# ESP32.net
KiCad netlist of a schematic drawn in Altium Designer
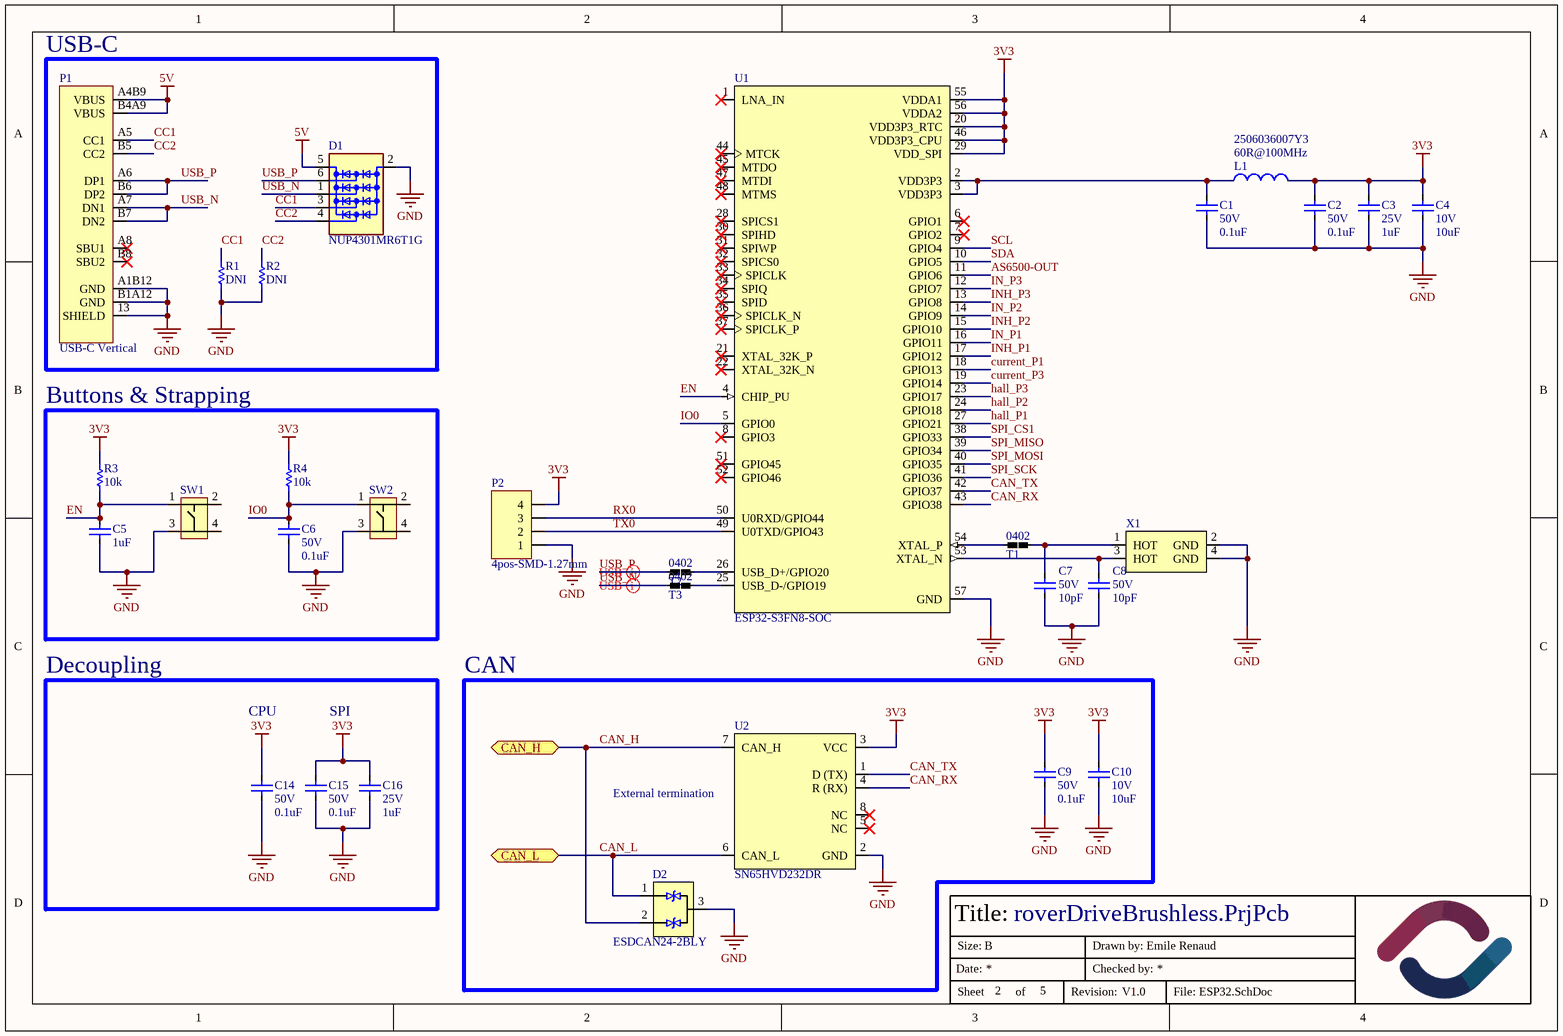
[diagram p0: ESP32.SchDoc]

(export (version "E")
  (design (tool "Eeschema 10.0.6"))
  (components
    (comp (ref "C1")
      (value "0.1uF")
      (footprint "CAPACITOR-0603")
      (description "Capacitor-0603-0.1uF-50V-X7R")
      (fields (field (name "VOLT") "50V"))
      (libsource (lib "Capacitors") (part "Capacitor-0603-0.1uF-50V-X7R"))
    )
    (comp (ref "C2")
      (value "0.1uF")
      (footprint "CAPACITOR-0603")
      (description "Capacitor-0603-0.1uF-50V-X7R")
      (fields (field (name "VOLT") "50V"))
      (libsource (lib "Capacitors") (part "Capacitor-0603-0.1uF-50V-X7R"))
    )
    (comp (ref "C3")
      (value "1uF")
      (footprint "CAPACITOR-0603")
      (description "Capacitor-0603-1uF-25V-X5R")
      (fields (field (name "VOLT") "25V"))
      (libsource (lib "Capacitors") (part "Capacitor-0603-1uF-25V-X5R"))
    )
    (comp (ref "C4")
      (value "10uF")
      (footprint "CAPACITOR-0603")
      (description "10 µF ±20% 10V Ceramic Capacitor X5R 0603 (1608 Metric)")
      (fields (field (name "VOLT") "10V") (field (name "Comment") "Capacitor-0603-10uF-10V-X5R"))
      (libsource (lib "Capacitors") (part "Capacitor-0603-10uF-10V-X5R"))
    )
    (comp (ref "C5")
      (value "1uF")
      (footprint "CAPACITOR-0603")
      (description "Capacitor-0603-1uF-25V-X5R")
      (libsource (lib "Capacitors") (part "Capacitor-0603-1uF-25V-X5R"))
    )
    (comp (ref "C6")
      (value "0.1uF")
      (footprint "CAPACITOR-0603")
      (description "Capacitor-0603-0.1uF-50V-X7R")
      (fields (field (name "VOLT") "50V"))
      (libsource (lib "Capacitors") (part "Capacitor-0603-0.1uF-50V-X7R"))
    )
    (comp (ref "C7")
      (value "10pF")
      (footprint "CAPACITOR-0402")
      (description "Capacitor-0402-10pF-50V-C0G")
      (fields (field (name "VOLT") "50V"))
      (libsource (lib "Capacitors") (part "Capacitor-0402-10pF-50V-C0G"))
    )
    (comp (ref "C8")
      (value "10pF")
      (footprint "CAPACITOR-0402")
      (description "Capacitor-0402-10pF-50V-C0G")
      (fields (field (name "VOLT") "50V"))
      (libsource (lib "Capacitors") (part "Capacitor-0402-10pF-50V-C0G"))
    )
    (comp (ref "C9")
      (value "0.1uF")
      (footprint "CAPACITOR-0603")
      (description "Capacitor-0603-0.1uF-50V-X7R")
      (fields (field (name "VOLT") "50V"))
      (libsource (lib "Capacitors") (part "Capacitor-0603-0.1uF-50V-X7R"))
    )
    (comp (ref "C10")
      (value "10uF")
      (footprint "CAPACITOR-0603")
      (description "10 µF ±20% 10V Ceramic Capacitor X5R 0603 (1608 Metric)")
      (fields (field (name "VOLT") "10V") (field (name "Comment") "Capacitor-0603-10uF-10V-X5R"))
      (libsource (lib "Capacitors") (part "Capacitor-0603-10uF-10V-X5R"))
    )
    (comp (ref "C14")
      (value "0.1uF")
      (footprint "CAPACITOR-0603")
      (description "Capacitor-0603-0.1uF-50V-X7R")
      (fields (field (name "VOLT") "50V"))
      (libsource (lib "Capacitors") (part "Capacitor-0603-0.1uF-50V-X7R"))
    )
    (comp (ref "C15")
      (value "0.1uF")
      (footprint "CAPACITOR-0603")
      (description "Capacitor-0603-0.1uF-50V-X7R")
      (fields (field (name "VOLT") "50V"))
      (libsource (lib "Capacitors") (part "Capacitor-0603-0.1uF-50V-X7R"))
    )
    (comp (ref "C16")
      (value "1uF")
      (footprint "CAPACITOR-0603")
      (description "Capacitor-0603-1uF-25V-X5R")
      (fields (field (name "VOLT") "25V"))
      (libsource (lib "Capacitors") (part "Capacitor-0603-1uF-25V-X5R"))
    )
    (comp (ref "D1")
      (value "NUP4301MR6T1G")
      (footprint "SOT-23-6")
      (description "4CH Clamp Ipp Tvs Diode Surface Mount SOT23-6 (SC74)")
      (libsource (lib "diodes") (part "NUP4301MR6T1G"))
    )
    (comp (ref "D2")
      (value "ESDCAN24-2BLY")
      (footprint "SOT-23-3")
      (description "55V Clamp 6A (8/20µs) Ipp Tvs Diode Surface Mount SOT-23")
      (libsource (lib "diodes-tvs") (part "ESDCAN24-2BLY"))
    )
    (comp (ref "L1")
      (value "2506036007Y3")
      (footprint "CAPACITOR-0603")
      (description "60 Ohms @ 100 MHz 1 Signal Line Ferrite Bead 0603 (1608 Metric) 3A 40mOhm")
      (fields (field (name "ALTIUM_VALUE") "60R@100MHz"))
      (libsource (lib "Inductors") (part "2506036007Y3"))
    )
    (comp (ref "P1")
      (value "USB-C Vertical")
      (footprint "GCT_USB4145-03-0230-C_REVA2")
      (description "USB4145-03-0230-C\r\n5A USB USB 2.0 Receptacle")
      (libsource (lib "PC-connector") (part "USB-C Vertical"))
    )
    (comp (ref "P2")
      (value "4pos-SMD-1.27mm")
      (footprint "HDR1X4-SMD-50mils")
      (description "4pos SMD 1.27mm")
      (libsource (lib "Header") (part "4pos-SMD-1.27mm"))
    )
    (comp (ref "R1")
      (value "DNI")
      (footprint "RESISTOR-0603")
      (description "0603 footprint DO NOT INSTALL")
      (fields (field (name "Comment") "Resistor-0603-5.1k"))
      (libsource (lib "Resistors") (part "Resistor-0603-DNI"))
    )
    (comp (ref "R2")
      (value "DNI")
      (footprint "RESISTOR-0603")
      (description "0603 footprint DO NOT INSTALL")
      (fields (field (name "Comment") "Resistor-0603-5.1k"))
      (libsource (lib "Resistors") (part "Resistor-0603-DNI"))
    )
    (comp (ref "R3")
      (value "10k")
      (footprint "Resistor-0603")
      (description "Resistor0603-10k")
      (fields (field (name "Comment") "SMT resistor"))
      (libsource (lib "Resistors") (part "Resistor0603-10k"))
    )
    (comp (ref "R4")
      (value "10k")
      (footprint "Resistor-0603")
      (description "Resistor0603-10k")
      (fields (field (name "Comment") "SMT resistor"))
      (libsource (lib "Resistors") (part "Resistor0603-10k"))
    )
    (comp (ref "SW1")
      (value "PTS815 SJM 250 SMTR LFS")
      (footprint "SW4_PTS815 SJM 250 SMTR LFS_CNK")
      (description "TACT 4.2 X 3.2, 2.5 MM H, 180GF,")
      (libsource (lib "THTPushButtonSwitches") (part "PTS815 SJM 250 SMTR LFS"))
    )
    (comp (ref "SW2")
      (value "PTS815 SJM 250 SMTR LFS")
      (footprint "SW4_PTS815 SJM 250 SMTR LFS_CNK")
      (description "TACT 4.2 X 3.2, 2.5 MM H, 180GF,")
      (libsource (lib "THTPushButtonSwitches") (part "PTS815 SJM 250 SMTR LFS"))
    )
    (comp (ref "T1")
      (value "NetTie_0402")
      (footprint "NetTie-0402")
      (libsource (lib "JumpersAndHoles") (part "NetTie_0402"))
    )
    (comp (ref "T2")
      (value "NetTie_0402")
      (footprint "NetTie-0402")
      (libsource (lib "JumpersAndHoles") (part "NetTie_0402"))
    )
    (comp (ref "T3")
      (value "NetTie_0402")
      (footprint "NetTie-0402")
      (libsource (lib "JumpersAndHoles") (part "NetTie_0402"))
    )
    (comp (ref "U1")
      (value "ESP32-S3FN8-SOC")
      (footprint "VFQFN-56 Exposed Pad")
      (fields (field (name "MF") "Espressif Systems") (field (name "MP") "ESP32-S3FN8"))
      (libsource (lib "Microcontrollers") (part "ESP32-S3FN8-SOC"))
    )
    (comp (ref "U2")
      (value "SN65HVD232DR")
      (footprint "SOIC-8")
      (description "1/1 Transceiver Half CANbus 8-SOIC")
      (libsource (lib "Transceiver") (part "SN65HVD232DR"))
    )
    (comp (ref "X1")
      (value "CX2016DB40000D0FLJCC")
      (footprint "4-SMD")
      (description "40 MHz ±10ppm Crystal 8pF 50 Ohms 4-SMD, No Lead")
      (libsource (lib "Crystals") (part "CX2016DB40000D0FLJCC"))
    )
  )
  (nets
    (net (code "1") (name "/AS6500-OUT") (class "Default")
      (node (ref "U1") (pin "11") (pinfunction "GPIO6_11") (pintype "bidirectional"))
    )
    (net (code "2") (name "/CAN_H") (class "Default")
      (node (ref "D2") (pin "2") (pinfunction "GND_2") (pintype "passive"))
      (node (ref "U2") (pin "7") (pinfunction "CAN_H_7") (pintype "passive"))
    )
    (net (code "3") (name "/CAN_L") (class "Default")
      (node (ref "D2") (pin "1") (pinfunction "L2_1") (pintype "passive"))
      (node (ref "U2") (pin "6") (pinfunction "CAN_L_6") (pintype "passive"))
    )
    (net (code "4") (name "/CAN_RX") (class "Default")
      (node (ref "U1") (pin "43") (pinfunction "GPIO38_43") (pintype "bidirectional"))
      (node (ref "U2") (pin "4") (pinfunction "R_(RX)_4") (pintype "passive"))
    )
    (net (code "5") (name "/CAN_TX") (class "Default")
      (node (ref "U1") (pin "42") (pinfunction "GPIO37_42") (pintype "bidirectional"))
      (node (ref "U2") (pin "1") (pinfunction "D_(TX)_1") (pintype "passive"))
    )
    (net (code "6") (name "/CC1") (class "Default")
      (node (ref "D1") (pin "3") (pinfunction "L3_3") (pintype "passive"))
      (node (ref "P1") (pin "A5") (pinfunction "CC1_A5") (pintype "passive"))
      (node (ref "R1") (pin "2") (pinfunction "2_2") (pintype "passive"))
    )
    (net (code "7") (name "/CC2") (class "Default")
      (node (ref "D1") (pin "4") (pinfunction "L4_4") (pintype "passive"))
      (node (ref "P1") (pin "B5") (pinfunction "CC2_B5") (pintype "passive"))
      (node (ref "R2") (pin "2") (pinfunction "2_2") (pintype "passive"))
    )
    (net (code "8") (name "/EN") (class "Default")
      (node (ref "C5") (pin "2") (pinfunction "2_2") (pintype "passive"))
      (node (ref "R3") (pin "1") (pinfunction "1_1") (pintype "passive"))
      (node (ref "SW1") (pin "1") (pinfunction "1_1") (pintype "passive"))
      (node (ref "U1") (pin "4") (pinfunction "CHIP_PU_4") (pintype "input"))
    )
    (net (code "9") (name "/INH_P1") (class "Default")
      (node (ref "U1") (pin "17") (pinfunction "GPIO12_17") (pintype "bidirectional"))
    )
    (net (code "10") (name "/INH_P2") (class "Default")
      (node (ref "U1") (pin "15") (pinfunction "GPIO10_15") (pintype "bidirectional"))
    )
    (net (code "11") (name "/INH_P3") (class "Default")
      (node (ref "U1") (pin "13") (pinfunction "GPIO8_13") (pintype "bidirectional"))
    )
    (net (code "12") (name "/IN_P1") (class "Default")
      (node (ref "U1") (pin "16") (pinfunction "GPIO11_16") (pintype "bidirectional"))
    )
    (net (code "13") (name "/IN_P2") (class "Default")
      (node (ref "U1") (pin "14") (pinfunction "GPIO9_14") (pintype "bidirectional"))
    )
    (net (code "14") (name "/IN_P3") (class "Default")
      (node (ref "U1") (pin "12") (pinfunction "GPIO7_12") (pintype "bidirectional"))
    )
    (net (code "15") (name "/IO0") (class "Default")
      (node (ref "C6") (pin "2") (pinfunction "2_2") (pintype "passive"))
      (node (ref "R4") (pin "1") (pinfunction "1_1") (pintype "passive"))
      (node (ref "SW2") (pin "1") (pinfunction "1_1") (pintype "passive"))
      (node (ref "U1") (pin "5") (pinfunction "GPIO0_5") (pintype "bidirectional"))
    )
    (net (code "16") (name "/RX0") (class "Default")
      (node (ref "P2") (pin "3") (pinfunction "3_3") (pintype "passive"))
      (node (ref "U1") (pin "50") (pinfunction "U0RXD/GPIO44_50") (pintype "bidirectional"))
    )
    (net (code "17") (name "/SCL") (class "Default")
      (node (ref "U1") (pin "9") (pinfunction "GPIO4_9") (pintype "bidirectional"))
    )
    (net (code "18") (name "/SDA") (class "Default")
      (node (ref "U1") (pin "10") (pinfunction "GPIO5_10") (pintype "bidirectional"))
    )
    (net (code "19") (name "/SPI_CS1") (class "Default")
      (node (ref "U1") (pin "38") (pinfunction "GPIO33_38") (pintype "bidirectional"))
    )
    (net (code "20") (name "/SPI_MISO") (class "Default")
      (node (ref "U1") (pin "39") (pinfunction "GPIO34_39") (pintype "bidirectional"))
    )
    (net (code "21") (name "/SPI_MOSI") (class "Default")
      (node (ref "U1") (pin "40") (pinfunction "GPIO35_40") (pintype "bidirectional"))
    )
    (net (code "22") (name "/SPI_SCK") (class "Default")
      (node (ref "U1") (pin "41") (pinfunction "GPIO36_41") (pintype "bidirectional"))
    )
    (net (code "23") (name "/TX0") (class "Default")
      (node (ref "P2") (pin "2") (pinfunction "2_2") (pintype "passive"))
      (node (ref "U1") (pin "49") (pinfunction "U0TXD/GPIO43_49") (pintype "bidirectional"))
    )
    (net (code "24") (name "/USB_N") (class "Default")
      (node (ref "D1") (pin "1") (pinfunction "L2_1") (pintype "passive"))
      (node (ref "P1") (pin "A7") (pinfunction "DN1_A7") (pintype "passive"))
      (node (ref "P1") (pin "B7") (pinfunction "DN2_B7") (pintype "passive"))
      (node (ref "T3") (pin "2") (pinfunction "2_2") (pintype "passive"))
    )
    (net (code "25") (name "/USB_P") (class "Default")
      (node (ref "D1") (pin "6") (pinfunction "L1_6") (pintype "passive"))
      (node (ref "P1") (pin "A6") (pinfunction "DP1_A6") (pintype "passive"))
      (node (ref "P1") (pin "B6") (pinfunction "DP2_B6") (pintype "passive"))
      (node (ref "T2") (pin "2") (pinfunction "2_2") (pintype "passive"))
    )
    (net (code "26") (name "/current_P1") (class "Default")
      (node (ref "U1") (pin "18") (pinfunction "GPIO13_18") (pintype "bidirectional"))
    )
    (net (code "27") (name "/current_P3") (class "Default")
      (node (ref "U1") (pin "19") (pinfunction "GPIO14_19") (pintype "bidirectional"))
    )
    (net (code "28") (name "/hall_P1") (class "Default")
      (node (ref "U1") (pin "27") (pinfunction "GPIO21_27") (pintype "bidirectional"))
    )
    (net (code "29") (name "/hall_P2") (class "Default")
      (node (ref "U1") (pin "24") (pinfunction "GPIO18_24") (pintype "bidirectional"))
    )
    (net (code "30") (name "/hall_P3") (class "Default")
      (node (ref "U1") (pin "23") (pinfunction "GPIO17_23") (pintype "bidirectional"))
    )
    (net (code "31") (name "3V3") (class "Default")
      (node (ref "C10") (pin "2") (pinfunction "2_2") (pintype "passive"))
      (node (ref "C14") (pin "2") (pinfunction "2_2") (pintype "passive"))
      (node (ref "C15") (pin "2") (pinfunction "2_2") (pintype "passive"))
      (node (ref "C16") (pin "2") (pinfunction "2_2") (pintype "passive"))
      (node (ref "C2") (pin "2") (pinfunction "2_2") (pintype "passive"))
      (node (ref "C3") (pin "2") (pinfunction "2_2") (pintype "passive"))
      (node (ref "C4") (pin "2") (pinfunction "2_2") (pintype "passive"))
      (node (ref "C9") (pin "2") (pinfunction "2_2") (pintype "passive"))
      (node (ref "L1") (pin "2") (pinfunction "2_2") (pintype "passive"))
      (node (ref "P2") (pin "4") (pinfunction "4_4") (pintype "passive"))
      (node (ref "R3") (pin "2") (pinfunction "2_2") (pintype "passive"))
      (node (ref "R4") (pin "2") (pinfunction "2_2") (pintype "passive"))
      (node (ref "U1") (pin "20") (pinfunction "VDD3P3_RTC_20") (pintype "power_in"))
      (node (ref "U1") (pin "29") (pinfunction "VDD_SPI_29") (pintype "power_in"))
      (node (ref "U1") (pin "46") (pinfunction "VDD3P3_CPU_46") (pintype "power_in"))
      (node (ref "U1") (pin "55") (pinfunction "VDDA1_55") (pintype "power_in"))
      (node (ref "U1") (pin "56") (pinfunction "VDDA2_56") (pintype "power_in"))
      (node (ref "U2") (pin "3") (pinfunction "VCC_3") (pintype "passive"))
    )
    (net (code "32") (name "5V") (class "Default")
      (node (ref "D1") (pin "5") (pinfunction "VDD_5") (pintype "passive"))
      (node (ref "P1") (pin "A4B9") (pinfunction "VBUS_A4B9") (pintype "passive"))
      (node (ref "P1") (pin "B4A9") (pinfunction "VBUS_B4A9") (pintype "passive"))
    )
    (net (code "33") (name "GND") (class "Default")
      (node (ref "C1") (pin "1") (pinfunction "1_1") (pintype "passive"))
      (node (ref "C10") (pin "1") (pinfunction "1_1") (pintype "passive"))
      (node (ref "C14") (pin "1") (pinfunction "1_1") (pintype "passive"))
      (node (ref "C15") (pin "1") (pinfunction "1_1") (pintype "passive"))
      (node (ref "C16") (pin "1") (pinfunction "1_1") (pintype "passive"))
      (node (ref "C2") (pin "1") (pinfunction "1_1") (pintype "passive"))
      (node (ref "C3") (pin "1") (pinfunction "1_1") (pintype "passive"))
      (node (ref "C4") (pin "1") (pinfunction "1_1") (pintype "passive"))
      (node (ref "C5") (pin "1") (pinfunction "1_1") (pintype "passive"))
      (node (ref "C6") (pin "1") (pinfunction "1_1") (pintype "passive"))
      (node (ref "C7") (pin "1") (pinfunction "1_1") (pintype "passive"))
      (node (ref "C8") (pin "1") (pinfunction "1_1") (pintype "passive"))
      (node (ref "C9") (pin "1") (pinfunction "1_1") (pintype "passive"))
      (node (ref "D1") (pin "2") (pinfunction "GND_2") (pintype "passive"))
      (node (ref "D2") (pin "3") (pinfunction "L3_3") (pintype "passive"))
      (node (ref "P1") (pin "13") (pinfunction "SHIELD_13") (pintype "passive"))
      (node (ref "P1") (pin "A1B12") (pinfunction "GND_A1B12") (pintype "passive"))
      (node (ref "P1") (pin "B1A12") (pinfunction "GND_B1A12") (pintype "passive"))
      (node (ref "P2") (pin "1") (pinfunction "1_1") (pintype "passive"))
      (node (ref "R1") (pin "1") (pinfunction "1_1") (pintype "passive"))
      (node (ref "R2") (pin "1") (pinfunction "1_1") (pintype "passive"))
      (node (ref "SW1") (pin "3") (pinfunction "3_3") (pintype "passive"))
      (node (ref "SW2") (pin "3") (pinfunction "3_3") (pintype "passive"))
      (node (ref "U1") (pin "57") (pinfunction "GND_57") (pintype "power_in"))
      (node (ref "U2") (pin "2") (pinfunction "GND_2") (pintype "passive"))
      (node (ref "X1") (pin "2") (pinfunction "GND_2") (pintype "passive"))
      (node (ref "X1") (pin "4") (pinfunction "GND_4") (pintype "passive"))
    )
    (net (code "34") (name "Net-(C1-Pad2)") (class "Default")
      (node (ref "C1") (pin "2") (pinfunction "2_2") (pintype "passive"))
      (node (ref "L1") (pin "1") (pinfunction "1_1") (pintype "passive"))
      (node (ref "U1") (pin "2") (pinfunction "VDD3P3_2") (pintype "power_in"))
      (node (ref "U1") (pin "3") (pinfunction "VDD3P3_3") (pintype "power_in"))
    )
    (net (code "35") (name "Net-(C7-Pad2)") (class "Default")
      (node (ref "C7") (pin "2") (pinfunction "2_2") (pintype "passive"))
      (node (ref "T1") (pin "1") (pinfunction "1_1") (pintype "passive"))
      (node (ref "X1") (pin "1") (pinfunction "HOT_1") (pintype "passive"))
    )
    (net (code "36") (name "Net-(U1-USB_D+{slash}GPIO20)") (class "Default")
      (node (ref "T2") (pin "1") (pinfunction "1_1") (pintype "passive"))
      (node (ref "U1") (pin "26") (pinfunction "USB_D+/GPIO20_26") (pintype "bidirectional"))
    )
    (net (code "37") (name "Net-(U1-USB_D-{slash}GPIO19)") (class "Default")
      (node (ref "T3") (pin "1") (pinfunction "1_1") (pintype "passive"))
      (node (ref "U1") (pin "25") (pinfunction "USB_D-/GPIO19_25") (pintype "bidirectional"))
    )
    (net (code "38") (name "Net-(U1-XTAL_N)") (class "Default")
      (node (ref "C8") (pin "2") (pinfunction "2_2") (pintype "passive"))
      (node (ref "U1") (pin "53") (pinfunction "XTAL_N_53") (pintype "output"))
      (node (ref "X1") (pin "3") (pinfunction "HOT_3") (pintype "passive"))
    )
    (net (code "39") (name "Net-(U1-XTAL_P)") (class "Default")
      (node (ref "T1") (pin "2") (pinfunction "2_2") (pintype "passive"))
      (node (ref "U1") (pin "54") (pinfunction "XTAL_P_54") (pintype "input"))
    )
    (net (code "40") (name "unconnected-(P1-SBU1-PadA8)") (class "Default")
      (node (ref "P1") (pin "A8") (pinfunction "SBU1_A8") (pintype "passive+no_connect"))
    )
    (net (code "41") (name "unconnected-(P1-SBU2-PadB8)") (class "Default")
      (node (ref "P1") (pin "B8") (pinfunction "SBU2_B8") (pintype "passive+no_connect"))
    )
    (net (code "42") (name "unconnected-(SW1-Pad2)") (class "Default")
      (node (ref "SW1") (pin "2") (pinfunction "2_2") (pintype "passive"))
    )
    (net (code "43") (name "unconnected-(SW1-Pad4)") (class "Default")
      (node (ref "SW1") (pin "4") (pinfunction "4_4") (pintype "passive"))
    )
    (net (code "44") (name "unconnected-(SW2-Pad2)") (class "Default")
      (node (ref "SW2") (pin "2") (pinfunction "2_2") (pintype "passive"))
    )
    (net (code "45") (name "unconnected-(SW2-Pad4)") (class "Default")
      (node (ref "SW2") (pin "4") (pinfunction "4_4") (pintype "passive"))
    )
    (net (code "46") (name "unconnected-(U1-GPIO1-Pad6)") (class "Default")
      (node (ref "U1") (pin "6") (pinfunction "GPIO1_6") (pintype "bidirectional+no_connect"))
    )
    (net (code "47") (name "unconnected-(U1-GPIO2-Pad7)") (class "Default")
      (node (ref "U1") (pin "7") (pinfunction "GPIO2_7") (pintype "bidirectional+no_connect"))
    )
    (net (code "48") (name "unconnected-(U1-GPIO3-Pad8)") (class "Default")
      (node (ref "U1") (pin "8") (pinfunction "GPIO3_8") (pintype "bidirectional+no_connect"))
    )
    (net (code "49") (name "unconnected-(U1-GPIO45-Pad51)") (class "Default")
      (node (ref "U1") (pin "51") (pinfunction "GPIO45_51") (pintype "bidirectional+no_connect"))
    )
    (net (code "50") (name "unconnected-(U1-GPIO46-Pad52)") (class "Default")
      (node (ref "U1") (pin "52") (pinfunction "GPIO46_52") (pintype "bidirectional+no_connect"))
    )
    (net (code "51") (name "unconnected-(U1-LNA_IN-Pad1)") (class "Default")
      (node (ref "U1") (pin "1") (pinfunction "LNA_IN_1") (pintype "bidirectional+no_connect"))
    )
    (net (code "52") (name "unconnected-(U1-MTCK-Pad44)") (class "Default")
      (node (ref "U1") (pin "44") (pinfunction "MTCK_44") (pintype "bidirectional+no_connect"))
    )
    (net (code "53") (name "unconnected-(U1-MTDI-Pad47)") (class "Default")
      (node (ref "U1") (pin "47") (pinfunction "MTDI_47") (pintype "bidirectional+no_connect"))
    )
    (net (code "54") (name "unconnected-(U1-MTDO-Pad45)") (class "Default")
      (node (ref "U1") (pin "45") (pinfunction "MTDO_45") (pintype "bidirectional+no_connect"))
    )
    (net (code "55") (name "unconnected-(U1-MTMS-Pad48)") (class "Default")
      (node (ref "U1") (pin "48") (pinfunction "MTMS_48") (pintype "bidirectional+no_connect"))
    )
    (net (code "56") (name "unconnected-(U1-SPICLK-Pad33)") (class "Default")
      (node (ref "U1") (pin "33") (pinfunction "SPICLK_33") (pintype "bidirectional+no_connect"))
    )
    (net (code "57") (name "unconnected-(U1-SPICLK_N-Pad36)") (class "Default")
      (node (ref "U1") (pin "36") (pinfunction "SPICLK_N_36") (pintype "bidirectional+no_connect"))
    )
    (net (code "58") (name "unconnected-(U1-SPICLK_P-Pad37)") (class "Default")
      (node (ref "U1") (pin "37") (pinfunction "SPICLK_P_37") (pintype "bidirectional+no_connect"))
    )
    (net (code "59") (name "unconnected-(U1-SPICS0-Pad32)") (class "Default")
      (node (ref "U1") (pin "32") (pinfunction "SPICS0_32") (pintype "bidirectional+no_connect"))
    )
    (net (code "60") (name "unconnected-(U1-SPICS1-Pad28)") (class "Default")
      (node (ref "U1") (pin "28") (pinfunction "SPICS1_28") (pintype "bidirectional+no_connect"))
    )
    (net (code "61") (name "unconnected-(U1-SPID-Pad35)") (class "Default")
      (node (ref "U1") (pin "35") (pinfunction "SPID_35") (pintype "bidirectional+no_connect"))
    )
    (net (code "62") (name "unconnected-(U1-SPIHD-Pad30)") (class "Default")
      (node (ref "U1") (pin "30") (pinfunction "SPIHD_30") (pintype "bidirectional+no_connect"))
    )
    (net (code "63") (name "unconnected-(U1-SPIQ-Pad34)") (class "Default")
      (node (ref "U1") (pin "34") (pinfunction "SPIQ_34") (pintype "bidirectional+no_connect"))
    )
    (net (code "64") (name "unconnected-(U1-SPIWP-Pad31)") (class "Default")
      (node (ref "U1") (pin "31") (pinfunction "SPIWP_31") (pintype "bidirectional+no_connect"))
    )
    (net (code "65") (name "unconnected-(U1-XTAL_32K_N-Pad22)") (class "Default")
      (node (ref "U1") (pin "22") (pinfunction "XTAL_32K_N_22") (pintype "bidirectional+no_connect"))
    )
    (net (code "66") (name "unconnected-(U1-XTAL_32K_P-Pad21)") (class "Default")
      (node (ref "U1") (pin "21") (pinfunction "XTAL_32K_P_21") (pintype "bidirectional+no_connect"))
    )
    (net (code "67") (name "unconnected-(U2-NC-Pad5)") (class "Default")
      (node (ref "U2") (pin "5") (pinfunction "NC_5") (pintype "passive+no_connect"))
    )
    (net (code "68") (name "unconnected-(U2-NC-Pad8)") (class "Default")
      (node (ref "U2") (pin "8") (pinfunction "NC_8") (pintype "passive+no_connect"))
    )
  )
)
